# podlewacz_v2.net
KiCad netlist of a schematic drawn in EAGLE
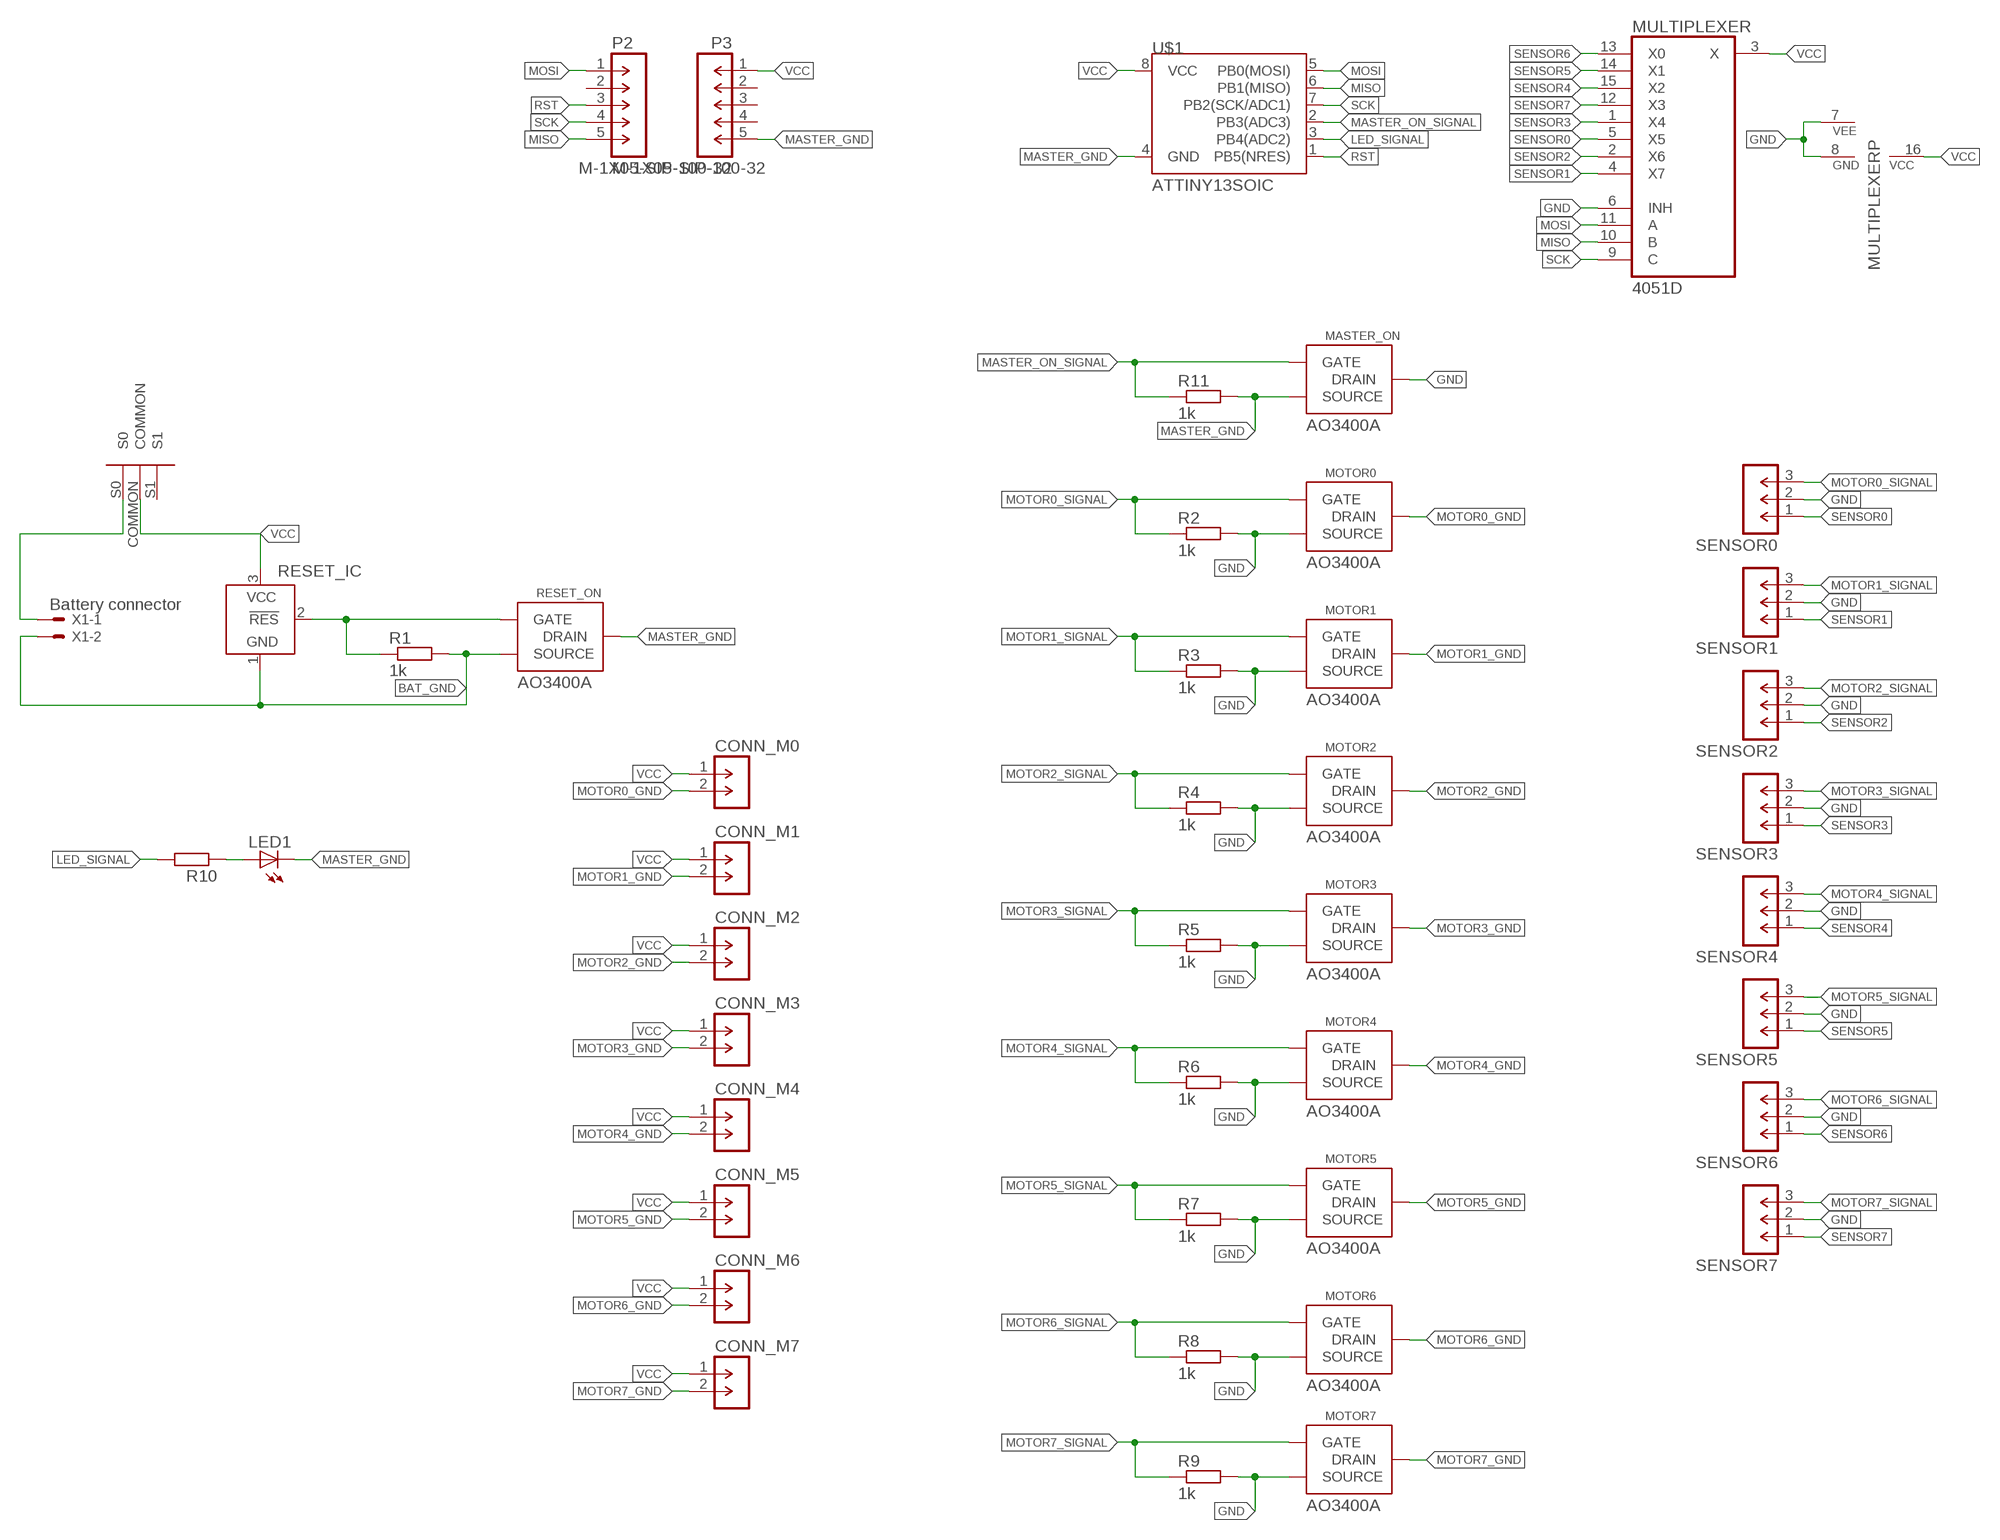
[diagram p0: schematic, sheet 1]

(export (version "E")
  (design (tool "Eeschema 10.0.6"))
  (components
    (comp (ref "CONN_M0")
      (value "M-1X02-SIP-100-32Y")
      (footprint "eagle-import:SIP-100-02-32Y")
      (libsource (lib "eagle-import") (part "M-1X02-SIP-100-32Y"))
    )
    (comp (ref "CONN_M1")
      (value "M-1X02-SIP-100-32Y")
      (footprint "eagle-import:SIP-100-02-32Y")
      (libsource (lib "eagle-import") (part "M-1X02-SIP-100-32Y"))
    )
    (comp (ref "CONN_M2")
      (value "M-1X02-SIP-100-32Y")
      (footprint "eagle-import:SIP-100-02-32Y")
      (libsource (lib "eagle-import") (part "M-1X02-SIP-100-32Y"))
    )
    (comp (ref "CONN_M3")
      (value "M-1X02-SIP-100-32Y")
      (footprint "eagle-import:SIP-100-02-32Y")
      (libsource (lib "eagle-import") (part "M-1X02-SIP-100-32Y"))
    )
    (comp (ref "CONN_M4")
      (value "M-1X02-SIP-100-32Y")
      (footprint "eagle-import:SIP-100-02-32Y")
      (libsource (lib "eagle-import") (part "M-1X02-SIP-100-32Y"))
    )
    (comp (ref "CONN_M5")
      (value "M-1X02-SIP-100-32Y")
      (footprint "eagle-import:SIP-100-02-32Y")
      (libsource (lib "eagle-import") (part "M-1X02-SIP-100-32Y"))
    )
    (comp (ref "CONN_M6")
      (value "M-1X02-SIP-100-32Y")
      (footprint "eagle-import:SIP-100-02-32Y")
      (libsource (lib "eagle-import") (part "M-1X02-SIP-100-32Y"))
    )
    (comp (ref "CONN_M7")
      (value "M-1X02-SIP-100-32Y")
      (footprint "eagle-import:SIP-100-02-32Y")
      (libsource (lib "eagle-import") (part "M-1X02-SIP-100-32Y"))
    )
    (comp (ref "LED1")
      (value "LEDCHIP-LED0805")
      (footprint "eagle-import:CHIP-LED0805")
      (libsource (lib "eagle-import") (part "LEDCHIP-LED0805"))
    )
    (comp (ref "MASTER_ON")
      (value "AO3400A")
      (footprint "eagle-import:SOT-23")
      (libsource (lib "eagle-import") (part "AO3400A"))
    )
    (comp (ref "MOTOR0")
      (value "AO3400A")
      (footprint "eagle-import:SOT-23")
      (libsource (lib "eagle-import") (part "AO3400A"))
    )
    (comp (ref "MOTOR1")
      (value "AO3400A")
      (footprint "eagle-import:SOT-23")
      (libsource (lib "eagle-import") (part "AO3400A"))
    )
    (comp (ref "MOTOR2")
      (value "AO3400A")
      (footprint "eagle-import:SOT-23")
      (libsource (lib "eagle-import") (part "AO3400A"))
    )
    (comp (ref "MOTOR3")
      (value "AO3400A")
      (footprint "eagle-import:SOT-23")
      (libsource (lib "eagle-import") (part "AO3400A"))
    )
    (comp (ref "MOTOR4")
      (value "AO3400A")
      (footprint "eagle-import:SOT-23")
      (libsource (lib "eagle-import") (part "AO3400A"))
    )
    (comp (ref "MOTOR5")
      (value "AO3400A")
      (footprint "eagle-import:SOT-23")
      (libsource (lib "eagle-import") (part "AO3400A"))
    )
    (comp (ref "MOTOR6")
      (value "AO3400A")
      (footprint "eagle-import:SOT-23")
      (libsource (lib "eagle-import") (part "AO3400A"))
    )
    (comp (ref "MOTOR7")
      (value "AO3400A")
      (footprint "eagle-import:SOT-23")
      (libsource (lib "eagle-import") (part "AO3400A"))
    )
    (comp (ref "MULTIPLEXER")
      (value "4051D")
      (footprint "eagle-import:SO16")
      (libsource (lib "eagle-import") (part "4051D"))
    )
    (comp (ref "P2")
      (value "M-1X05-SIP-100-32")
      (footprint "eagle-import:SIP-100-05-32")
      (libsource (lib "eagle-import") (part "M-1X05-SIP-100-32"))
    )
    (comp (ref "P3")
      (value "M-1X05-SIP-100-32")
      (footprint "eagle-import:SIP-100-05-32")
      (libsource (lib "eagle-import") (part "M-1X05-SIP-100-32"))
    )
    (comp (ref "R1")
      (value "1k")
      (footprint "eagle-import:M1206")
      (libsource (lib "eagle-import") (part "R-EU_M1206"))
    )
    (comp (ref "R2")
      (value "1k")
      (footprint "eagle-import:M1206")
      (libsource (lib "eagle-import") (part "R-EU_M1206"))
    )
    (comp (ref "R3")
      (value "1k")
      (footprint "eagle-import:M1206")
      (libsource (lib "eagle-import") (part "R-EU_M1206"))
    )
    (comp (ref "R4")
      (value "1k")
      (footprint "eagle-import:M1206")
      (libsource (lib "eagle-import") (part "R-EU_M1206"))
    )
    (comp (ref "R5")
      (value "1k")
      (footprint "eagle-import:M1206")
      (libsource (lib "eagle-import") (part "R-EU_M1206"))
    )
    (comp (ref "R6")
      (value "1k")
      (footprint "eagle-import:M1206")
      (libsource (lib "eagle-import") (part "R-EU_M1206"))
    )
    (comp (ref "R7")
      (value "1k")
      (footprint "eagle-import:M1206")
      (libsource (lib "eagle-import") (part "R-EU_M1206"))
    )
    (comp (ref "R8")
      (value "1k")
      (footprint "eagle-import:M1206")
      (libsource (lib "eagle-import") (part "R-EU_M1206"))
    )
    (comp (ref "R9")
      (value "1k")
      (footprint "eagle-import:M1206")
      (libsource (lib "eagle-import") (part "R-EU_M1206"))
    )
    (comp (ref "R10")
      (value "R-EU_M0805")
      (footprint "eagle-import:M0805")
      (libsource (lib "eagle-import") (part "R-EU_M0805"))
    )
    (comp (ref "R11")
      (value "1k")
      (footprint "eagle-import:M1206")
      (libsource (lib "eagle-import") (part "R-EU_M1206"))
    )
    (comp (ref "RESET_IC")
      (value "TCM809")
      (footprint "eagle-import:SOT23B-3")
      (fields (field (name "MF") "MICROCHIP") (field (name "MPN") "TCM809MENB713"))
      (libsource (lib "eagle-import") (part "TCM809"))
    )
    (comp (ref "RESET_ON")
      (value "AO3400A")
      (footprint "eagle-import:SOT-23")
      (libsource (lib "eagle-import") (part "AO3400A"))
    )
    (comp (ref "SENSOR0")
      (value "M-1X03-SIP-100-32Y")
      (footprint "eagle-import:SIP-100-03-32Y")
      (libsource (lib "eagle-import") (part "M-1X03-SIP-100-32Y"))
    )
    (comp (ref "SENSOR1")
      (value "M-1X03-SIP-100-32Y")
      (footprint "eagle-import:SIP-100-03-32Y")
      (libsource (lib "eagle-import") (part "M-1X03-SIP-100-32Y"))
    )
    (comp (ref "SENSOR2")
      (value "M-1X03-SIP-100-32Y")
      (footprint "eagle-import:SIP-100-03-32Y")
      (libsource (lib "eagle-import") (part "M-1X03-SIP-100-32Y"))
    )
    (comp (ref "SENSOR3")
      (value "M-1X03-SIP-100-32Y")
      (footprint "eagle-import:SIP-100-03-32Y")
      (libsource (lib "eagle-import") (part "M-1X03-SIP-100-32Y"))
    )
    (comp (ref "SENSOR4")
      (value "M-1X03-SIP-100-32Y")
      (footprint "eagle-import:SIP-100-03-32Y")
      (libsource (lib "eagle-import") (part "M-1X03-SIP-100-32Y"))
    )
    (comp (ref "SENSOR5")
      (value "M-1X03-SIP-100-32Y")
      (footprint "eagle-import:SIP-100-03-32Y")
      (libsource (lib "eagle-import") (part "M-1X03-SIP-100-32Y"))
    )
    (comp (ref "SENSOR6")
      (value "M-1X03-SIP-100-32Y")
      (footprint "eagle-import:SIP-100-03-32Y")
      (libsource (lib "eagle-import") (part "M-1X03-SIP-100-32Y"))
    )
    (comp (ref "SENSOR7")
      (value "M-1X03-SIP-100-32Y")
      (footprint "eagle-import:SIP-100-03-32Y")
      (libsource (lib "eagle-import") (part "M-1X03-SIP-100-32Y"))
    )
    (comp (ref "U$1")
      (value "ATTINY13SOIC")
      (footprint "eagle-import:SO08")
      (libsource (lib "eagle-import") (part "ATTINY13SOIC"))
    )
    (comp (ref "U$2")
      (value "SPDT_SLIDE_SWITCH_2_PITCH")
      (footprint "eagle-import:SPDT_SLIDE_SWITCH_2_PITCH")
      (libsource (lib "eagle-import") (part "SPDT_SLIDE_SWITCH_2_PITCH"))
    )
    (comp (ref "X1")
      (value "Battery connector")
      (footprint "eagle-import:22-23-2021")
      (fields (field (name "MF") "MOLEX") (field (name "MPN") "22-23-2021"))
      (libsource (lib "eagle-import") (part "22-23-2021"))
    )
  )
  (nets
    (net (code "1") (name "BAT_GND") (class "Default")
      (node (ref "R1") (pin "2") (pinfunction "2_2") (pintype "passive"))
      (node (ref "RESET_IC") (pin "1") (pinfunction "GND_1") (pintype "power_in"))
      (node (ref "RESET_ON") (pin "2") (pinfunction "SOURCE_2") (pintype "bidirectional"))
      (node (ref "X1") (pin "2") (pinfunction "S_2") (pintype "passive"))
    )
    (net (code "2") (name "GND") (class "Default")
      (node (ref "MASTER_ON") (pin "3") (pinfunction "DRAIN_3") (pintype "bidirectional"))
      (node (ref "MOTOR0") (pin "2") (pinfunction "SOURCE_2") (pintype "bidirectional"))
      (node (ref "MOTOR1") (pin "2") (pinfunction "SOURCE_2") (pintype "bidirectional"))
      (node (ref "MOTOR2") (pin "2") (pinfunction "SOURCE_2") (pintype "bidirectional"))
      (node (ref "MOTOR3") (pin "2") (pinfunction "SOURCE_2") (pintype "bidirectional"))
      (node (ref "MOTOR4") (pin "2") (pinfunction "SOURCE_2") (pintype "bidirectional"))
      (node (ref "MOTOR5") (pin "2") (pinfunction "SOURCE_2") (pintype "bidirectional"))
      (node (ref "MOTOR6") (pin "2") (pinfunction "SOURCE_2") (pintype "bidirectional"))
      (node (ref "MOTOR7") (pin "2") (pinfunction "SOURCE_2") (pintype "bidirectional"))
      (node (ref "MULTIPLEXER") (pin "6") (pinfunction "INH_6") (pintype "input"))
      (node (ref "MULTIPLEXER") (pin "7") (pinfunction "VEE_7") (pintype "power_in"))
      (node (ref "MULTIPLEXER") (pin "8") (pinfunction "GND_8") (pintype "power_in"))
      (node (ref "R2") (pin "2") (pinfunction "2_2") (pintype "passive"))
      (node (ref "R3") (pin "2") (pinfunction "2_2") (pintype "passive"))
      (node (ref "R4") (pin "2") (pinfunction "2_2") (pintype "passive"))
      (node (ref "R5") (pin "2") (pinfunction "2_2") (pintype "passive"))
      (node (ref "R6") (pin "2") (pinfunction "2_2") (pintype "passive"))
      (node (ref "R7") (pin "2") (pinfunction "2_2") (pintype "passive"))
      (node (ref "R8") (pin "2") (pinfunction "2_2") (pintype "passive"))
      (node (ref "R9") (pin "2") (pinfunction "2_2") (pintype "passive"))
      (node (ref "SENSOR0") (pin "2") (pinfunction "2_2") (pintype "passive"))
      (node (ref "SENSOR1") (pin "2") (pinfunction "2_2") (pintype "passive"))
      (node (ref "SENSOR2") (pin "2") (pinfunction "2_2") (pintype "passive"))
      (node (ref "SENSOR3") (pin "2") (pinfunction "2_2") (pintype "passive"))
      (node (ref "SENSOR4") (pin "2") (pinfunction "2_2") (pintype "passive"))
      (node (ref "SENSOR5") (pin "2") (pinfunction "2_2") (pintype "passive"))
      (node (ref "SENSOR6") (pin "2") (pinfunction "2_2") (pintype "passive"))
      (node (ref "SENSOR7") (pin "2") (pinfunction "2_2") (pintype "passive"))
    )
    (net (code "3") (name "LED_SIGNAL") (class "Default")
      (node (ref "R10") (pin "2") (pinfunction "2_2") (pintype "passive"))
      (node (ref "U$1") (pin "3") (pinfunction "PB4(ADC2)_3") (pintype "bidirectional"))
    )
    (net (code "4") (name "MASTER_GND") (class "Default")
      (node (ref "LED1") (pin "C") (pinfunction "C_C") (pintype "passive"))
      (node (ref "MASTER_ON") (pin "2") (pinfunction "SOURCE_2") (pintype "bidirectional"))
      (node (ref "P3") (pin "5") (pinfunction "5_5") (pintype "passive"))
      (node (ref "R11") (pin "2") (pinfunction "2_2") (pintype "passive"))
      (node (ref "RESET_ON") (pin "3") (pinfunction "DRAIN_3") (pintype "bidirectional"))
      (node (ref "U$1") (pin "4") (pinfunction "GND_4") (pintype "bidirectional"))
    )
    (net (code "5") (name "MASTER_ON_SIGNAL") (class "Default")
      (node (ref "MASTER_ON") (pin "1") (pinfunction "GATE_1") (pintype "bidirectional"))
      (node (ref "R11") (pin "1") (pinfunction "1_1") (pintype "passive"))
      (node (ref "U$1") (pin "2") (pinfunction "PB3(ADC3)_2") (pintype "bidirectional"))
    )
    (net (code "6") (name "MISO") (class "Default")
      (node (ref "MULTIPLEXER") (pin "10") (pinfunction "B_10") (pintype "input"))
      (node (ref "P2") (pin "5") (pinfunction "5_5") (pintype "passive"))
      (node (ref "U$1") (pin "6") (pinfunction "PB1(MISO)_6") (pintype "bidirectional"))
    )
    (net (code "7") (name "MOSI") (class "Default")
      (node (ref "MULTIPLEXER") (pin "11") (pinfunction "A_11") (pintype "input"))
      (node (ref "P2") (pin "1") (pinfunction "1_1") (pintype "passive"))
      (node (ref "U$1") (pin "5") (pinfunction "PB0(MOSI)_5") (pintype "bidirectional"))
    )
    (net (code "8") (name "MOTOR0_GND") (class "Default")
      (node (ref "CONN_M0") (pin "2") (pinfunction "2_2") (pintype "passive"))
      (node (ref "MOTOR0") (pin "3") (pinfunction "DRAIN_3") (pintype "bidirectional"))
    )
    (net (code "9") (name "MOTOR0_SIGNAL") (class "Default")
      (node (ref "MOTOR0") (pin "1") (pinfunction "GATE_1") (pintype "bidirectional"))
      (node (ref "R2") (pin "1") (pinfunction "1_1") (pintype "passive"))
      (node (ref "SENSOR0") (pin "3") (pinfunction "3_3") (pintype "passive"))
    )
    (net (code "10") (name "MOTOR1_GND") (class "Default")
      (node (ref "CONN_M1") (pin "2") (pinfunction "2_2") (pintype "passive"))
      (node (ref "MOTOR1") (pin "3") (pinfunction "DRAIN_3") (pintype "bidirectional"))
    )
    (net (code "11") (name "MOTOR1_SIGNAL") (class "Default")
      (node (ref "MOTOR1") (pin "1") (pinfunction "GATE_1") (pintype "bidirectional"))
      (node (ref "R3") (pin "1") (pinfunction "1_1") (pintype "passive"))
      (node (ref "SENSOR1") (pin "3") (pinfunction "3_3") (pintype "passive"))
    )
    (net (code "12") (name "MOTOR2_GND") (class "Default")
      (node (ref "CONN_M2") (pin "2") (pinfunction "2_2") (pintype "passive"))
      (node (ref "MOTOR2") (pin "3") (pinfunction "DRAIN_3") (pintype "bidirectional"))
    )
    (net (code "13") (name "MOTOR2_SIGNAL") (class "Default")
      (node (ref "MOTOR2") (pin "1") (pinfunction "GATE_1") (pintype "bidirectional"))
      (node (ref "R4") (pin "1") (pinfunction "1_1") (pintype "passive"))
      (node (ref "SENSOR2") (pin "3") (pinfunction "3_3") (pintype "passive"))
    )
    (net (code "14") (name "MOTOR3_GND") (class "Default")
      (node (ref "CONN_M3") (pin "2") (pinfunction "2_2") (pintype "passive"))
      (node (ref "MOTOR3") (pin "3") (pinfunction "DRAIN_3") (pintype "bidirectional"))
    )
    (net (code "15") (name "MOTOR3_SIGNAL") (class "Default")
      (node (ref "MOTOR3") (pin "1") (pinfunction "GATE_1") (pintype "bidirectional"))
      (node (ref "R5") (pin "1") (pinfunction "1_1") (pintype "passive"))
      (node (ref "SENSOR3") (pin "3") (pinfunction "3_3") (pintype "passive"))
    )
    (net (code "16") (name "MOTOR4_GND") (class "Default")
      (node (ref "CONN_M4") (pin "2") (pinfunction "2_2") (pintype "passive"))
      (node (ref "MOTOR4") (pin "3") (pinfunction "DRAIN_3") (pintype "bidirectional"))
    )
    (net (code "17") (name "MOTOR4_SIGNAL") (class "Default")
      (node (ref "MOTOR4") (pin "1") (pinfunction "GATE_1") (pintype "bidirectional"))
      (node (ref "R6") (pin "1") (pinfunction "1_1") (pintype "passive"))
      (node (ref "SENSOR4") (pin "3") (pinfunction "3_3") (pintype "passive"))
    )
    (net (code "18") (name "MOTOR5_GND") (class "Default")
      (node (ref "CONN_M5") (pin "2") (pinfunction "2_2") (pintype "passive"))
      (node (ref "MOTOR5") (pin "3") (pinfunction "DRAIN_3") (pintype "bidirectional"))
    )
    (net (code "19") (name "MOTOR5_SIGNAL") (class "Default")
      (node (ref "MOTOR5") (pin "1") (pinfunction "GATE_1") (pintype "bidirectional"))
      (node (ref "R7") (pin "1") (pinfunction "1_1") (pintype "passive"))
      (node (ref "SENSOR5") (pin "3") (pinfunction "3_3") (pintype "passive"))
    )
    (net (code "20") (name "MOTOR6_GND") (class "Default")
      (node (ref "CONN_M6") (pin "2") (pinfunction "2_2") (pintype "passive"))
      (node (ref "MOTOR6") (pin "3") (pinfunction "DRAIN_3") (pintype "bidirectional"))
    )
    (net (code "21") (name "MOTOR6_SIGNAL") (class "Default")
      (node (ref "MOTOR6") (pin "1") (pinfunction "GATE_1") (pintype "bidirectional"))
      (node (ref "R8") (pin "1") (pinfunction "1_1") (pintype "passive"))
      (node (ref "SENSOR6") (pin "3") (pinfunction "3_3") (pintype "passive"))
    )
    (net (code "22") (name "MOTOR7_GND") (class "Default")
      (node (ref "CONN_M7") (pin "2") (pinfunction "2_2") (pintype "passive"))
      (node (ref "MOTOR7") (pin "3") (pinfunction "DRAIN_3") (pintype "bidirectional"))
    )
    (net (code "23") (name "MOTOR7_SIGNAL") (class "Default")
      (node (ref "MOTOR7") (pin "1") (pinfunction "GATE_1") (pintype "bidirectional"))
      (node (ref "R9") (pin "1") (pinfunction "1_1") (pintype "passive"))
      (node (ref "SENSOR7") (pin "3") (pinfunction "3_3") (pintype "passive"))
    )
    (net (code "24") (name "Net-(LED1-PadA)") (class "Default")
      (node (ref "LED1") (pin "A") (pinfunction "A_A") (pintype "passive"))
      (node (ref "R10") (pin "1") (pinfunction "1_1") (pintype "passive"))
    )
    (net (code "25") (name "Net-(RESET_IC-~{RES})") (class "Default")
      (node (ref "R1") (pin "1") (pinfunction "1_1") (pintype "passive"))
      (node (ref "RESET_IC") (pin "2") (pinfunction "~{RES}_2") (pintype "output"))
      (node (ref "RESET_ON") (pin "1") (pinfunction "GATE_1") (pintype "bidirectional"))
    )
    (net (code "26") (name "Net-(X1A-S)") (class "Default")
      (node (ref "U$2") (pin "S0") (pinfunction "S0_S0") (pintype "bidirectional"))
      (node (ref "X1") (pin "1") (pinfunction "S_1") (pintype "passive"))
    )
    (net (code "27") (name "RST") (class "Default")
      (node (ref "P2") (pin "3") (pinfunction "3_3") (pintype "passive"))
      (node (ref "U$1") (pin "1") (pinfunction "PB5(NRES)_1") (pintype "bidirectional"))
    )
    (net (code "28") (name "SCK") (class "Default")
      (node (ref "MULTIPLEXER") (pin "9") (pinfunction "C_9") (pintype "input"))
      (node (ref "P2") (pin "4") (pinfunction "4_4") (pintype "passive"))
      (node (ref "U$1") (pin "7") (pinfunction "PB2(SCK/ADC1)_7") (pintype "bidirectional"))
    )
    (net (code "29") (name "SENSOR0") (class "Default")
      (node (ref "MULTIPLEXER") (pin "5") (pinfunction "X5_5") (pintype "bidirectional"))
      (node (ref "SENSOR0") (pin "1") (pinfunction "1_1") (pintype "passive"))
    )
    (net (code "30") (name "SENSOR1") (class "Default")
      (node (ref "MULTIPLEXER") (pin "4") (pinfunction "X7_4") (pintype "bidirectional"))
      (node (ref "SENSOR1") (pin "1") (pinfunction "1_1") (pintype "passive"))
    )
    (net (code "31") (name "SENSOR2") (class "Default")
      (node (ref "MULTIPLEXER") (pin "2") (pinfunction "X6_2") (pintype "bidirectional"))
      (node (ref "SENSOR2") (pin "1") (pinfunction "1_1") (pintype "passive"))
    )
    (net (code "32") (name "SENSOR3") (class "Default")
      (node (ref "MULTIPLEXER") (pin "1") (pinfunction "X4_1") (pintype "bidirectional"))
      (node (ref "SENSOR3") (pin "1") (pinfunction "1_1") (pintype "passive"))
    )
    (net (code "33") (name "SENSOR4") (class "Default")
      (node (ref "MULTIPLEXER") (pin "15") (pinfunction "X2_15") (pintype "bidirectional"))
      (node (ref "SENSOR4") (pin "1") (pinfunction "1_1") (pintype "passive"))
    )
    (net (code "34") (name "SENSOR5") (class "Default")
      (node (ref "MULTIPLEXER") (pin "14") (pinfunction "X1_14") (pintype "bidirectional"))
      (node (ref "SENSOR5") (pin "1") (pinfunction "1_1") (pintype "passive"))
    )
    (net (code "35") (name "SENSOR6") (class "Default")
      (node (ref "MULTIPLEXER") (pin "13") (pinfunction "X0_13") (pintype "bidirectional"))
      (node (ref "SENSOR6") (pin "1") (pinfunction "1_1") (pintype "passive"))
    )
    (net (code "36") (name "SENSOR7") (class "Default")
      (node (ref "MULTIPLEXER") (pin "12") (pinfunction "X3_12") (pintype "bidirectional"))
      (node (ref "SENSOR7") (pin "1") (pinfunction "1_1") (pintype "passive"))
    )
    (net (code "37") (name "VCC") (class "Default")
      (node (ref "CONN_M0") (pin "1") (pinfunction "1_1") (pintype "passive"))
      (node (ref "CONN_M1") (pin "1") (pinfunction "1_1") (pintype "passive"))
      (node (ref "CONN_M2") (pin "1") (pinfunction "1_1") (pintype "passive"))
      (node (ref "CONN_M3") (pin "1") (pinfunction "1_1") (pintype "passive"))
      (node (ref "CONN_M4") (pin "1") (pinfunction "1_1") (pintype "passive"))
      (node (ref "CONN_M5") (pin "1") (pinfunction "1_1") (pintype "passive"))
      (node (ref "CONN_M6") (pin "1") (pinfunction "1_1") (pintype "passive"))
      (node (ref "CONN_M7") (pin "1") (pinfunction "1_1") (pintype "passive"))
      (node (ref "MULTIPLEXER") (pin "16") (pinfunction "VCC_16") (pintype "power_in"))
      (node (ref "MULTIPLEXER") (pin "3") (pinfunction "X_3") (pintype "bidirectional"))
      (node (ref "P3") (pin "1") (pinfunction "1_1") (pintype "passive"))
      (node (ref "RESET_IC") (pin "3") (pinfunction "VCC_3") (pintype "power_in"))
      (node (ref "U$1") (pin "8") (pinfunction "VCC_8") (pintype "bidirectional"))
      (node (ref "U$2") (pin "COMMON") (pinfunction "COMMON_COMMON") (pintype "bidirectional"))
    )
    (net (code "38") (name "unconnected-(P2-Pad2)") (class "Default")
      (node (ref "P2") (pin "2") (pinfunction "2_2") (pintype "passive"))
    )
    (net (code "39") (name "unconnected-(P3-Pad2)") (class "Default")
      (node (ref "P3") (pin "2") (pinfunction "2_2") (pintype "passive"))
    )
    (net (code "40") (name "unconnected-(P3-Pad3)") (class "Default")
      (node (ref "P3") (pin "3") (pinfunction "3_3") (pintype "passive"))
    )
    (net (code "41") (name "unconnected-(P3-Pad4)") (class "Default")
      (node (ref "P3") (pin "4") (pinfunction "4_4") (pintype "passive"))
    )
    (net (code "42") (name "unconnected-(U$2-PadS1)") (class "Default")
      (node (ref "U$2") (pin "S1") (pinfunction "S1_S1") (pintype "bidirectional"))
    )
  )
)
